# CRT_Control_Board.net
KiCad netlist of a schematic drawn in EAGLE
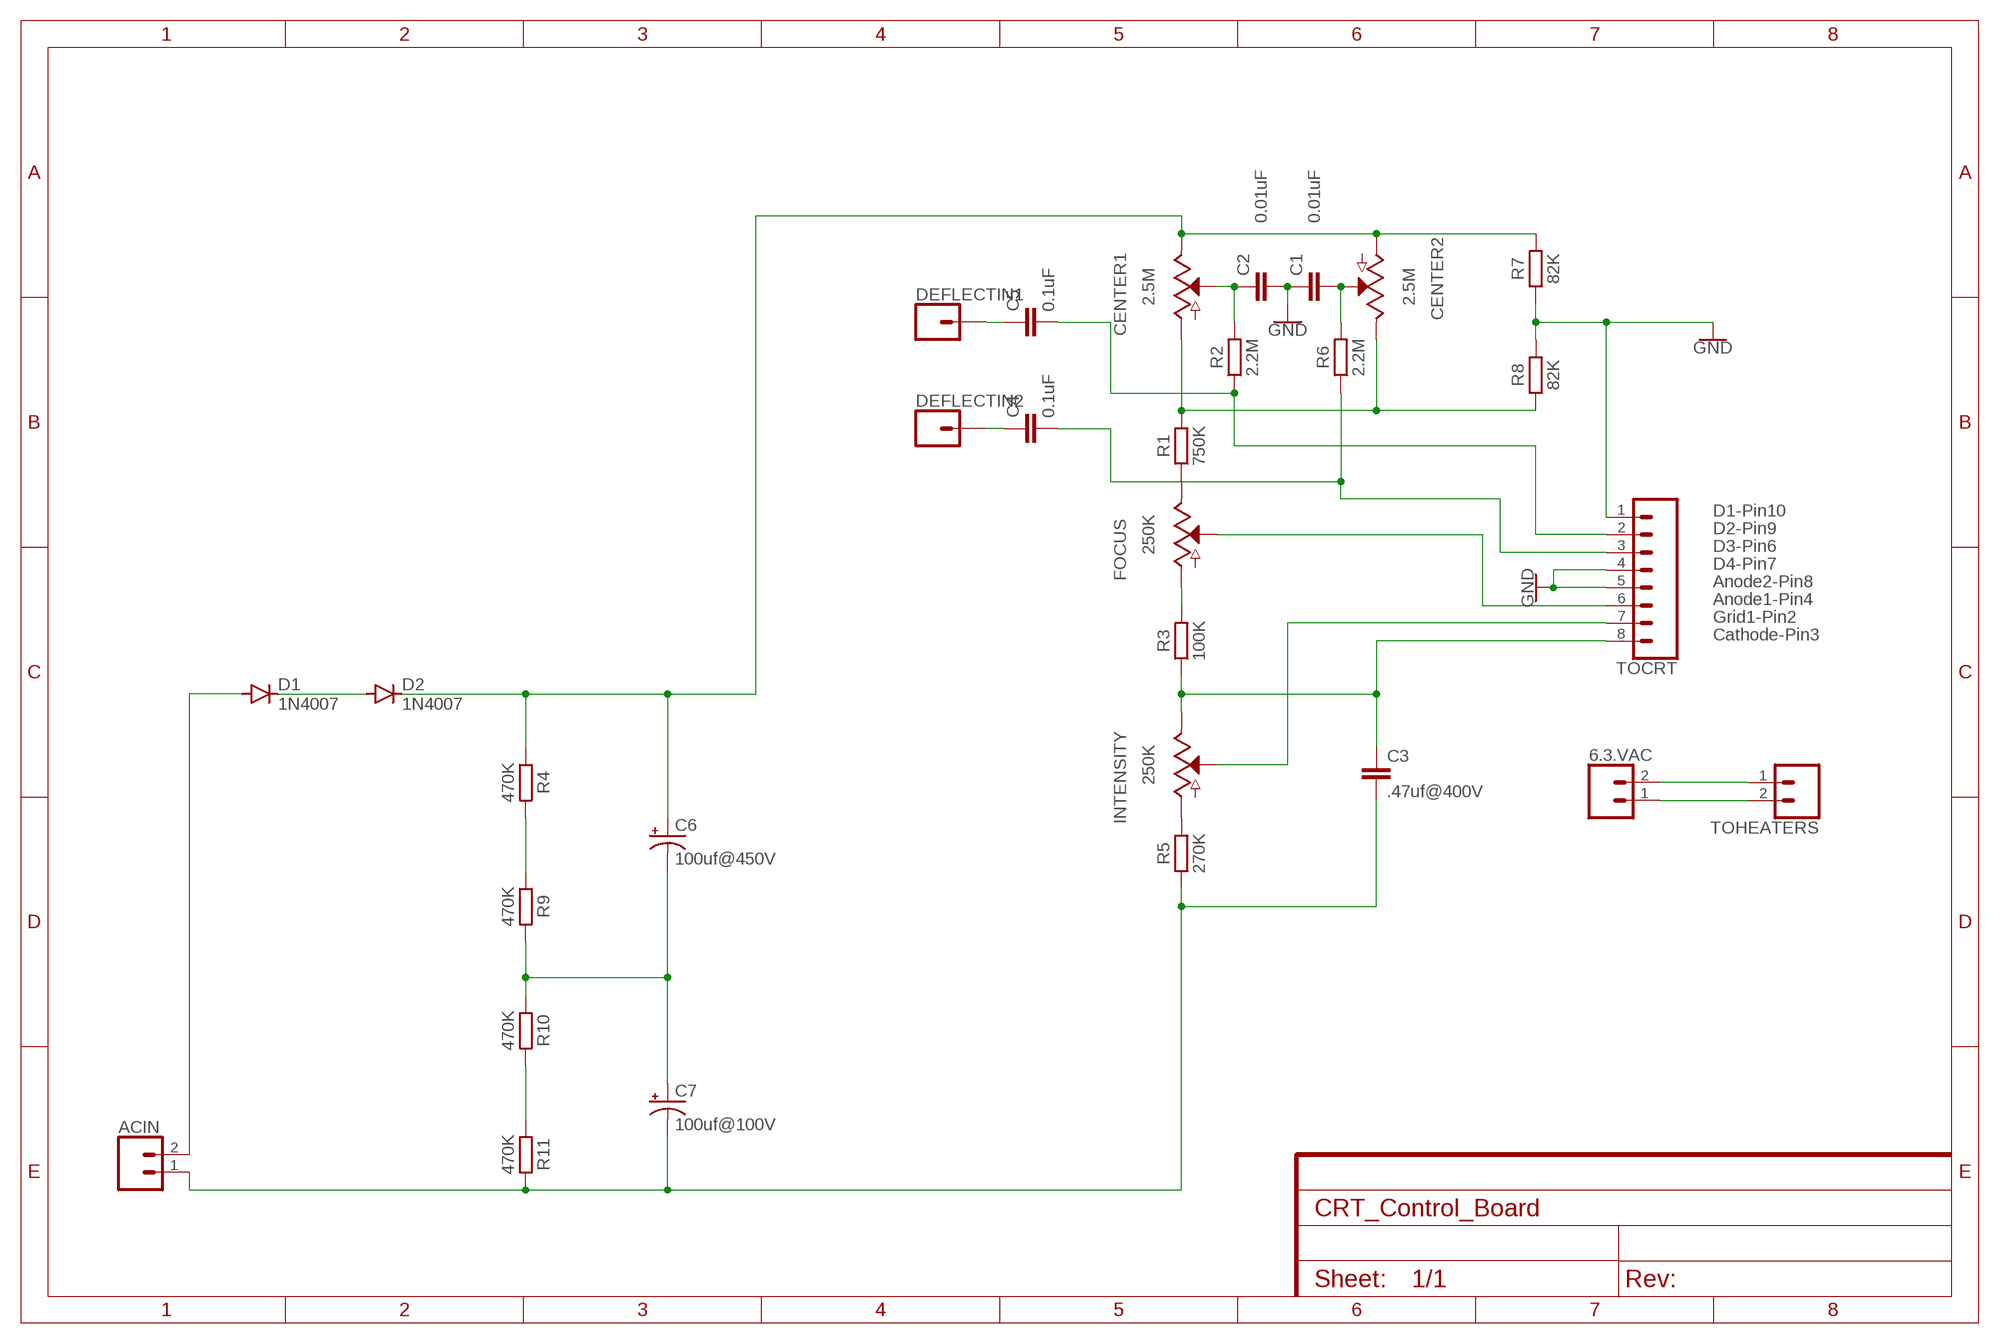
[diagram p0: schematic, sheet 1]

(export (version "E")
  (design (tool "Eeschema 10.0.6"))
  (components
    (comp (ref "6.3.VAC")
      (value "CONN_02")
      (footprint "eagle-import:1X02")
      (libsource (lib "eagle-import") (part "CONN_02"))
    )
    (comp (ref "ACIN")
      (value "CONN_02")
      (footprint "eagle-import:1X02")
      (libsource (lib "eagle-import") (part "CONN_02"))
    )
    (comp (ref "C1")
      (value "0.01uF")
      (footprint "eagle-import:CAP-PTH-SMALL-KIT")
      (libsource (lib "eagle-import") (part "0.1UF-KIT-EZ-50V-20%"))
    )
    (comp (ref "C2")
      (value "0.01uF")
      (footprint "eagle-import:CAP-PTH-SMALL-KIT")
      (libsource (lib "eagle-import") (part "0.1UF-KIT-EZ-50V-20%"))
    )
    (comp (ref "C3")
      (value ".47uf@400V")
      (footprint "eagle-import:CAP-PTH-SMALL-KIT")
      (libsource (lib "eagle-import") (part "0.1UF-KIT-EZ-50V-20%"))
    )
    (comp (ref "C4")
      (value "0.1uF")
      (footprint "eagle-import:CAP-PTH-SMALL-KIT")
      (libsource (lib "eagle-import") (part "0.1UF-KIT-EZ-50V-20%"))
    )
    (comp (ref "C5")
      (value "0.1uF")
      (footprint "eagle-import:CAP-PTH-SMALL-KIT")
      (libsource (lib "eagle-import") (part "0.1UF-KIT-EZ-50V-20%"))
    )
    (comp (ref "C6")
      (value "100uf@450V")
      (footprint "eagle-import:E5-6")
      (libsource (lib "eagle-import") (part "CPOL-USE5-6"))
    )
    (comp (ref "C7")
      (value "100uf@100V")
      (footprint "eagle-import:E5-6")
      (libsource (lib "eagle-import") (part "CPOL-USE5-6"))
    )
    (comp (ref "CENTER1")
      (value "2.5M")
      (footprint "eagle-import:POT-PTH-ALPS")
      (libsource (lib "eagle-import") (part "POTENTIOMETER-PTH-9MM-1/20W-20%"))
    )
    (comp (ref "CENTER2")
      (value "2.5M")
      (footprint "eagle-import:POT-PTH-ALPS")
      (libsource (lib "eagle-import") (part "POTENTIOMETER-PTH-9MM-1/20W-20%"))
    )
    (comp (ref "D1")
      (value "1N4007")
      (footprint "eagle-import:DO41-10")
      (libsource (lib "eagle-import") (part "1N4004"))
    )
    (comp (ref "D2")
      (value "1N4007")
      (footprint "eagle-import:DO41-10")
      (libsource (lib "eagle-import") (part "1N4004"))
    )
    (comp (ref "DEFLECTIN1")
      (value "CONN_01PTH_LONGPAD")
      (footprint "eagle-import:1X01_LONGPAD")
      (libsource (lib "eagle-import") (part "CONN_01PTH_LONGPAD"))
    )
    (comp (ref "DEFLECTIN2")
      (value "CONN_01PTH_LONGPAD")
      (footprint "eagle-import:1X01_LONGPAD")
      (libsource (lib "eagle-import") (part "CONN_01PTH_LONGPAD"))
    )
    (comp (ref "FOCUS")
      (value "250K")
      (footprint "eagle-import:POT-PTH-ALPS")
      (libsource (lib "eagle-import") (part "POTENTIOMETER-PTH-9MM-1/20W-20%"))
    )
    (comp (ref "INTENSITY")
      (value "250K")
      (footprint "eagle-import:POT-PTH-ALPS")
      (libsource (lib "eagle-import") (part "POTENTIOMETER-PTH-9MM-1/20W-20%"))
    )
    (comp (ref "R1")
      (value "750K")
      (footprint "eagle-import:RESAD1176W63L850D250B")
      (libsource (lib "eagle-import") (part "RAXIAL-11.7MM-PITCH_"))
    )
    (comp (ref "R2")
      (value "2.2M")
      (footprint "eagle-import:RESAD1176W63L850D250B")
      (libsource (lib "eagle-import") (part "RAXIAL-11.7MM-PITCH_"))
    )
    (comp (ref "R3")
      (value "100K")
      (footprint "eagle-import:RESAD1176W63L850D250B")
      (libsource (lib "eagle-import") (part "RAXIAL-11.7MM-PITCH_"))
    )
    (comp (ref "R4")
      (value "470K")
      (footprint "eagle-import:RESAD1176W63L850D250B")
      (libsource (lib "eagle-import") (part "RAXIAL-11.7MM-PITCH_"))
    )
    (comp (ref "R5")
      (value "270K")
      (footprint "eagle-import:RESAD1176W63L850D250B")
      (libsource (lib "eagle-import") (part "RAXIAL-11.7MM-PITCH_"))
    )
    (comp (ref "R6")
      (value "2.2M")
      (footprint "eagle-import:RESAD1176W63L850D250B")
      (libsource (lib "eagle-import") (part "RAXIAL-11.7MM-PITCH_"))
    )
    (comp (ref "R7")
      (value "82K")
      (footprint "eagle-import:RESAD1176W63L850D250B")
      (libsource (lib "eagle-import") (part "RAXIAL-11.7MM-PITCH_"))
    )
    (comp (ref "R8")
      (value "82K")
      (footprint "eagle-import:RESAD1176W63L850D250B")
      (libsource (lib "eagle-import") (part "RAXIAL-11.7MM-PITCH_"))
    )
    (comp (ref "R9")
      (value "470K")
      (footprint "eagle-import:RESAD1176W63L850D250B")
      (libsource (lib "eagle-import") (part "RAXIAL-11.7MM-PITCH_"))
    )
    (comp (ref "R10")
      (value "470K")
      (footprint "eagle-import:RESAD1176W63L850D250B")
      (libsource (lib "eagle-import") (part "RAXIAL-11.7MM-PITCH_"))
    )
    (comp (ref "R11")
      (value "470K")
      (footprint "eagle-import:RESAD1176W63L850D250B")
      (libsource (lib "eagle-import") (part "RAXIAL-11.7MM-PITCH_"))
    )
    (comp (ref "TOCRT")
      (value "CONN_08LONGPADS")
      (footprint "eagle-import:1X08_LONGPADS")
      (libsource (lib "eagle-import") (part "CONN_08LONGPADS"))
    )
    (comp (ref "TOHEATERS")
      (value "CONN_02")
      (footprint "eagle-import:1X02")
      (libsource (lib "eagle-import") (part "CONN_02"))
    )
  )
  (nets
    (net (code "1") (name "GND") (class "Default")
      (node (ref "C1") (pin "1") (pinfunction "1_1") (pintype "passive"))
      (node (ref "C2") (pin "2") (pinfunction "2_2") (pintype "passive"))
      (node (ref "R7") (pin "1") (pinfunction "1_1") (pintype "passive"))
      (node (ref "R8") (pin "2") (pinfunction "2_2") (pintype "passive"))
      (node (ref "TOCRT") (pin "1") (pinfunction "1_1") (pintype "passive"))
      (node (ref "TOCRT") (pin "4") (pinfunction "4_4") (pintype "passive"))
      (node (ref "TOCRT") (pin "5") (pinfunction "5_5") (pintype "passive"))
    )
    (net (code "2") (name "Net-(6.3.VAC-Pad1)") (class "Default")
      (node (ref "6.3.VAC") (pin "1") (pinfunction "1_1") (pintype "passive"))
      (node (ref "TOHEATERS") (pin "2") (pinfunction "2_2") (pintype "passive"))
    )
    (net (code "3") (name "Net-(6.3.VAC-Pad2)") (class "Default")
      (node (ref "6.3.VAC") (pin "2") (pinfunction "2_2") (pintype "passive"))
      (node (ref "TOHEATERS") (pin "1") (pinfunction "1_1") (pintype "passive"))
    )
    (net (code "4") (name "Net-(ACIN-Pad1)") (class "Default")
      (node (ref "ACIN") (pin "1") (pinfunction "1_1") (pintype "passive"))
      (node (ref "C3") (pin "2") (pinfunction "2_2") (pintype "passive"))
      (node (ref "C7") (pin "-") (pinfunction "-_-") (pintype "passive"))
      (node (ref "R11") (pin "2") (pinfunction "2_2") (pintype "passive"))
      (node (ref "R5") (pin "1") (pinfunction "1_1") (pintype "passive"))
    )
    (net (code "5") (name "Net-(ACIN-Pad2)") (class "Default")
      (node (ref "ACIN") (pin "2") (pinfunction "2_2") (pintype "passive"))
      (node (ref "D1") (pin "A") (pinfunction "A_A") (pintype "passive"))
    )
    (net (code "6") (name "Net-(C4-Pad1)") (class "Default")
      (node (ref "C4") (pin "1") (pinfunction "1_1") (pintype "passive"))
      (node (ref "DEFLECTIN2") (pin "1") (pinfunction "1_1") (pintype "passive"))
    )
    (net (code "7") (name "Net-(C4-Pad2)") (class "Default")
      (node (ref "C4") (pin "2") (pinfunction "2_2") (pintype "passive"))
      (node (ref "R6") (pin "1") (pinfunction "1_1") (pintype "passive"))
      (node (ref "TOCRT") (pin "3") (pinfunction "3_3") (pintype "passive"))
    )
    (net (code "8") (name "Net-(C5-Pad1)") (class "Default")
      (node (ref "C5") (pin "1") (pinfunction "1_1") (pintype "passive"))
      (node (ref "DEFLECTIN1") (pin "1") (pinfunction "1_1") (pintype "passive"))
    )
    (net (code "9") (name "Net-(C5-Pad2)") (class "Default")
      (node (ref "C5") (pin "2") (pinfunction "2_2") (pintype "passive"))
      (node (ref "R2") (pin "1") (pinfunction "1_1") (pintype "passive"))
      (node (ref "TOCRT") (pin "2") (pinfunction "2_2") (pintype "passive"))
    )
    (net (code "10") (name "Net-(C6-Pad-)") (class "Default")
      (node (ref "C6") (pin "-") (pinfunction "-_-") (pintype "passive"))
      (node (ref "C7") (pin "+") (pinfunction "+_+") (pintype "passive"))
      (node (ref "R10") (pin "1") (pinfunction "1_1") (pintype "passive"))
      (node (ref "R9") (pin "2") (pinfunction "2_2") (pintype "passive"))
    )
    (net (code "11") (name "Net-(CENTER1-A)") (class "Default")
      (node (ref "CENTER1") (pin "P$3") (pinfunction "A_P$3") (pintype "passive"))
      (node (ref "CENTER2") (pin "P$1") (pinfunction "E_P$1") (pintype "passive"))
      (node (ref "R1") (pin "2") (pinfunction "2_2") (pintype "passive"))
      (node (ref "R8") (pin "1") (pinfunction "1_1") (pintype "passive"))
    )
    (net (code "12") (name "Net-(CENTER1-E)") (class "Default")
      (node (ref "C6") (pin "+") (pinfunction "+_+") (pintype "passive"))
      (node (ref "CENTER1") (pin "P$1") (pinfunction "E_P$1") (pintype "passive"))
      (node (ref "CENTER2") (pin "P$3") (pinfunction "A_P$3") (pintype "passive"))
      (node (ref "D2") (pin "C") (pinfunction "C_C") (pintype "passive"))
      (node (ref "R4") (pin "1") (pinfunction "1_1") (pintype "passive"))
      (node (ref "R7") (pin "2") (pinfunction "2_2") (pintype "passive"))
    )
    (net (code "13") (name "Net-(CENTER1-S)") (class "Default")
      (node (ref "C2") (pin "1") (pinfunction "1_1") (pintype "passive"))
      (node (ref "CENTER1") (pin "P$2") (pinfunction "S_P$2") (pintype "passive"))
      (node (ref "R2") (pin "2") (pinfunction "2_2") (pintype "passive"))
    )
    (net (code "14") (name "Net-(CENTER2-S)") (class "Default")
      (node (ref "C1") (pin "2") (pinfunction "2_2") (pintype "passive"))
      (node (ref "CENTER2") (pin "P$2") (pinfunction "S_P$2") (pintype "passive"))
      (node (ref "R6") (pin "2") (pinfunction "2_2") (pintype "passive"))
    )
    (net (code "15") (name "Net-(D1-PadC)") (class "Default")
      (node (ref "D1") (pin "C") (pinfunction "C_C") (pintype "passive"))
      (node (ref "D2") (pin "A") (pinfunction "A_A") (pintype "passive"))
    )
    (net (code "16") (name "Net-(FOCUS-A)") (class "Default")
      (node (ref "FOCUS") (pin "P$3") (pinfunction "A_P$3") (pintype "passive"))
      (node (ref "R3") (pin "2") (pinfunction "2_2") (pintype "passive"))
    )
    (net (code "17") (name "Net-(FOCUS-E)") (class "Default")
      (node (ref "FOCUS") (pin "P$1") (pinfunction "E_P$1") (pintype "passive"))
      (node (ref "R1") (pin "1") (pinfunction "1_1") (pintype "passive"))
    )
    (net (code "18") (name "Net-(FOCUS-S)") (class "Default")
      (node (ref "FOCUS") (pin "P$2") (pinfunction "S_P$2") (pintype "passive"))
      (node (ref "TOCRT") (pin "6") (pinfunction "6_6") (pintype "passive"))
    )
    (net (code "19") (name "Net-(INTENSITY-A)") (class "Default")
      (node (ref "INTENSITY") (pin "P$3") (pinfunction "A_P$3") (pintype "passive"))
      (node (ref "R5") (pin "2") (pinfunction "2_2") (pintype "passive"))
    )
    (net (code "20") (name "Net-(INTENSITY-E)") (class "Default")
      (node (ref "C3") (pin "1") (pinfunction "1_1") (pintype "passive"))
      (node (ref "INTENSITY") (pin "P$1") (pinfunction "E_P$1") (pintype "passive"))
      (node (ref "R3") (pin "1") (pinfunction "1_1") (pintype "passive"))
      (node (ref "TOCRT") (pin "8") (pinfunction "8_8") (pintype "passive"))
    )
    (net (code "21") (name "Net-(INTENSITY-S)") (class "Default")
      (node (ref "INTENSITY") (pin "P$2") (pinfunction "S_P$2") (pintype "passive"))
      (node (ref "TOCRT") (pin "7") (pinfunction "7_7") (pintype "passive"))
    )
    (net (code "22") (name "Net-(R4-Pad2)") (class "Default")
      (node (ref "R4") (pin "2") (pinfunction "2_2") (pintype "passive"))
      (node (ref "R9") (pin "1") (pinfunction "1_1") (pintype "passive"))
    )
    (net (code "23") (name "Net-(R10-Pad2)") (class "Default")
      (node (ref "R10") (pin "2") (pinfunction "2_2") (pintype "passive"))
      (node (ref "R11") (pin "1") (pinfunction "1_1") (pintype "passive"))
    )
  )
)
